# USB_Interlock.net
KiCad netlist of a schematic drawn in EAGLE
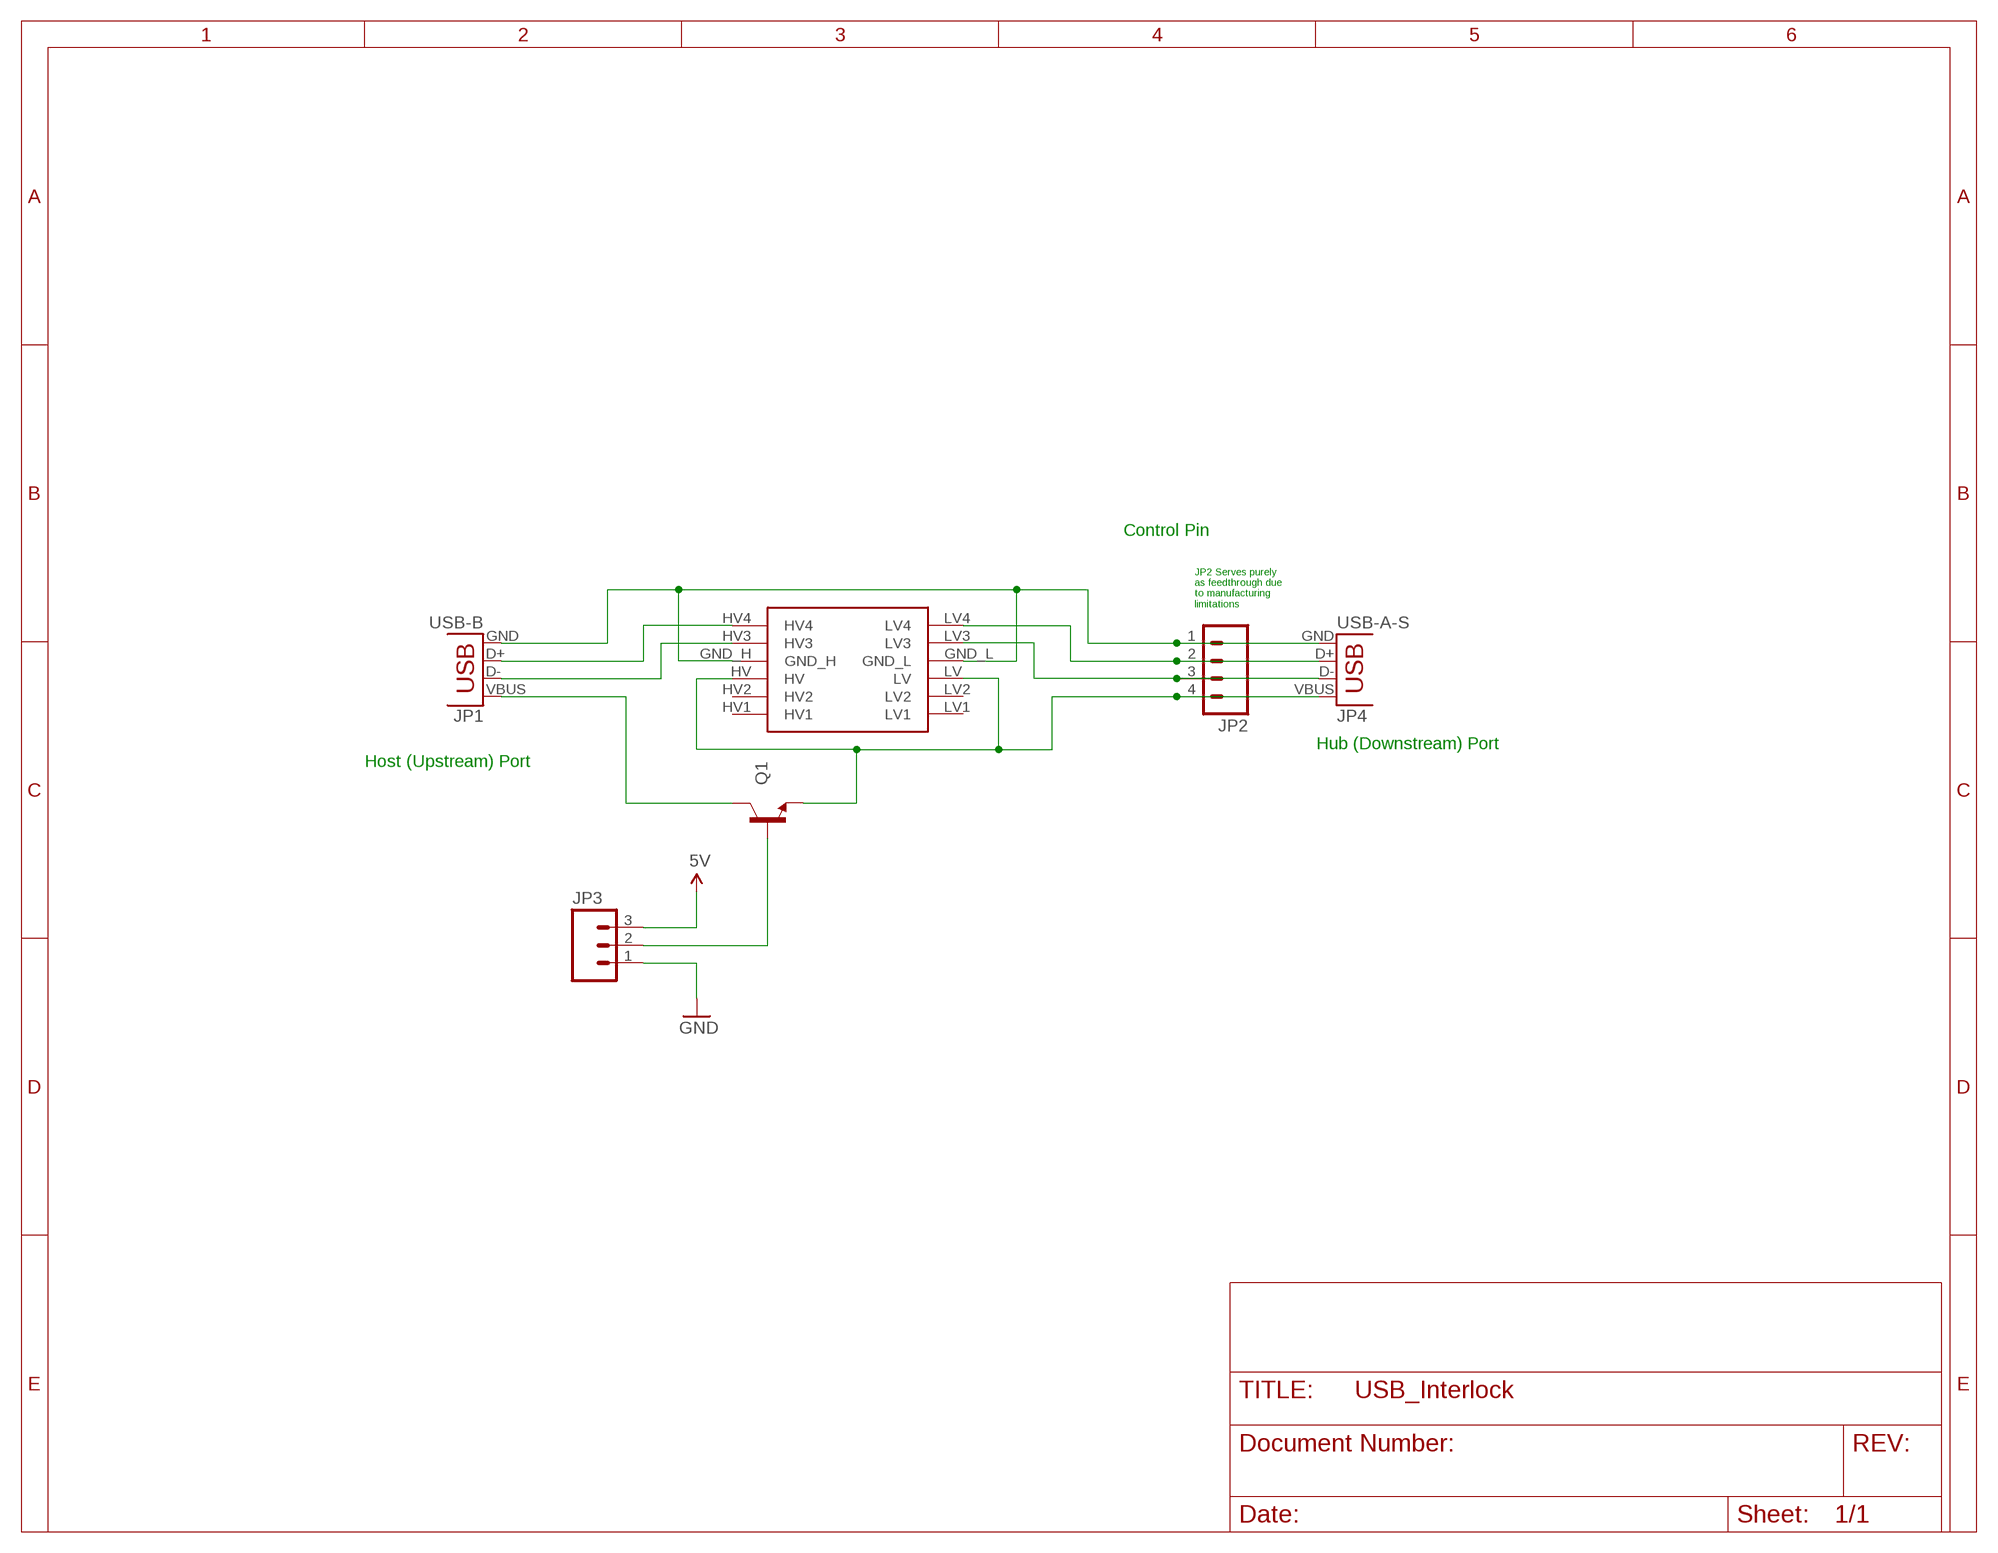
[diagram p0: schematic, sheet 1]

(export (version "E")
  (design (tool "Eeschema 10.0.6"))
  (components
    (comp (ref "JP1")
      (value "USB-B")
      (footprint "eagle-import:USB-B-PTH")
      (libsource (lib "eagle-import") (part "USBPTH"))
    )
    (comp (ref "JP2")
      (value "M04LONGPADS")
      (footprint "eagle-import:1X04_LONGPADS")
      (libsource (lib "eagle-import") (part "M04LONGPADS"))
    )
    (comp (ref "JP3")
      (value "M03LONGPADS")
      (footprint "eagle-import:1X03_LONGPADS")
      (libsource (lib "eagle-import") (part "M03LONGPADS"))
    )
    (comp (ref "JP4")
      (value "USB-A-S")
      (footprint "eagle-import:USB-A-S")
      (libsource (lib "eagle-import") (part "USB-A-S"))
    )
    (comp (ref "Q1")
      (value "TRANSISTOR_NPNBC547")
      (footprint "eagle-import:TO-92-AMMO")
      (libsource (lib "eagle-import") (part "TRANSISTOR_NPNBC547"))
    )
    (comp (ref "U$1")
      (value "LOGIC_LEVEL_CONVERTER")
      (footprint "eagle-import:LOGIC_LEVEL_CONVERTER")
      (libsource (lib "eagle-import") (part "LOGIC_LEVEL_CONVERTER"))
    )
  )
  (nets
    (net (code "1") (name "5V") (class "Default")
      (node (ref "JP3") (pin "3") (pinfunction "3_3") (pintype "passive"))
    )
    (net (code "2") (name "GND") (class "Default")
      (node (ref "JP1") (pin "GND") (pinfunction "GND_GND") (pintype "bidirectional"))
      (node (ref "JP2") (pin "1") (pinfunction "1_1") (pintype "passive"))
      (node (ref "JP3") (pin "1") (pinfunction "1_1") (pintype "passive"))
      (node (ref "JP4") (pin "GND") (pinfunction "GND_GND") (pintype "bidirectional"))
      (node (ref "U$1") (pin "GND_H") (pinfunction "GND_H_GND_H") (pintype "bidirectional"))
      (node (ref "U$1") (pin "GND_L") (pinfunction "GND_L_GND_L") (pintype "bidirectional"))
    )
    (net (code "3") (name "Net-(JP1-PadD+)") (class "Default")
      (node (ref "JP1") (pin "D+") (pinfunction "D+_D+") (pintype "bidirectional"))
      (node (ref "U$1") (pin "HV4") (pinfunction "HV4_HV4") (pintype "bidirectional"))
    )
    (net (code "4") (name "Net-(JP1-PadD-)") (class "Default")
      (node (ref "JP1") (pin "D-") (pinfunction "D-_D-") (pintype "bidirectional"))
      (node (ref "U$1") (pin "HV3") (pinfunction "HV3_HV3") (pintype "bidirectional"))
    )
    (net (code "5") (name "Net-(JP2-Pad2)") (class "Default")
      (node (ref "JP2") (pin "2") (pinfunction "2_2") (pintype "passive"))
      (node (ref "JP4") (pin "D+") (pinfunction "D+_D+") (pintype "bidirectional"))
      (node (ref "U$1") (pin "LV4") (pinfunction "LV4_LV4") (pintype "bidirectional"))
    )
    (net (code "6") (name "Net-(JP2-Pad3)") (class "Default")
      (node (ref "JP2") (pin "3") (pinfunction "3_3") (pintype "passive"))
      (node (ref "JP4") (pin "D-") (pinfunction "D-_D-") (pintype "bidirectional"))
      (node (ref "U$1") (pin "LV3") (pinfunction "LV3_LV3") (pintype "bidirectional"))
    )
    (net (code "7") (name "Net-(Q1-B)") (class "Default")
      (node (ref "JP3") (pin "2") (pinfunction "2_2") (pintype "passive"))
      (node (ref "Q1") (pin "2") (pinfunction "B_2") (pintype "passive"))
    )
    (net (code "8") (name "Net-(Q1-C)") (class "Default")
      (node (ref "JP1") (pin "VBUS") (pinfunction "VBUS_VBUS") (pintype "bidirectional"))
      (node (ref "Q1") (pin "1") (pinfunction "C_1") (pintype "passive"))
    )
    (net (code "9") (name "Net-(Q1-E)") (class "Default")
      (node (ref "JP2") (pin "4") (pinfunction "4_4") (pintype "passive"))
      (node (ref "JP4") (pin "VBUS") (pinfunction "VBUS_VBUS") (pintype "bidirectional"))
      (node (ref "Q1") (pin "3") (pinfunction "E_3") (pintype "passive"))
      (node (ref "U$1") (pin "HV") (pinfunction "HV_HV") (pintype "bidirectional"))
      (node (ref "U$1") (pin "LV") (pinfunction "LV_LV") (pintype "bidirectional"))
    )
    (net (code "10") (name "unconnected-(U$1-PadHV1)") (class "Default")
      (node (ref "U$1") (pin "HV1") (pinfunction "HV1_HV1") (pintype "bidirectional"))
    )
    (net (code "11") (name "unconnected-(U$1-PadHV2)") (class "Default")
      (node (ref "U$1") (pin "HV2") (pinfunction "HV2_HV2") (pintype "bidirectional"))
    )
    (net (code "12") (name "unconnected-(U$1-PadLV1)") (class "Default")
      (node (ref "U$1") (pin "LV1") (pinfunction "LV1_LV1") (pintype "bidirectional"))
    )
    (net (code "13") (name "unconnected-(U$1-PadLV2)") (class "Default")
      (node (ref "U$1") (pin "LV2") (pinfunction "LV2_LV2") (pintype "bidirectional"))
    )
  )
)
